# main.net
KiCad netlist of a schematic drawn in EAGLE
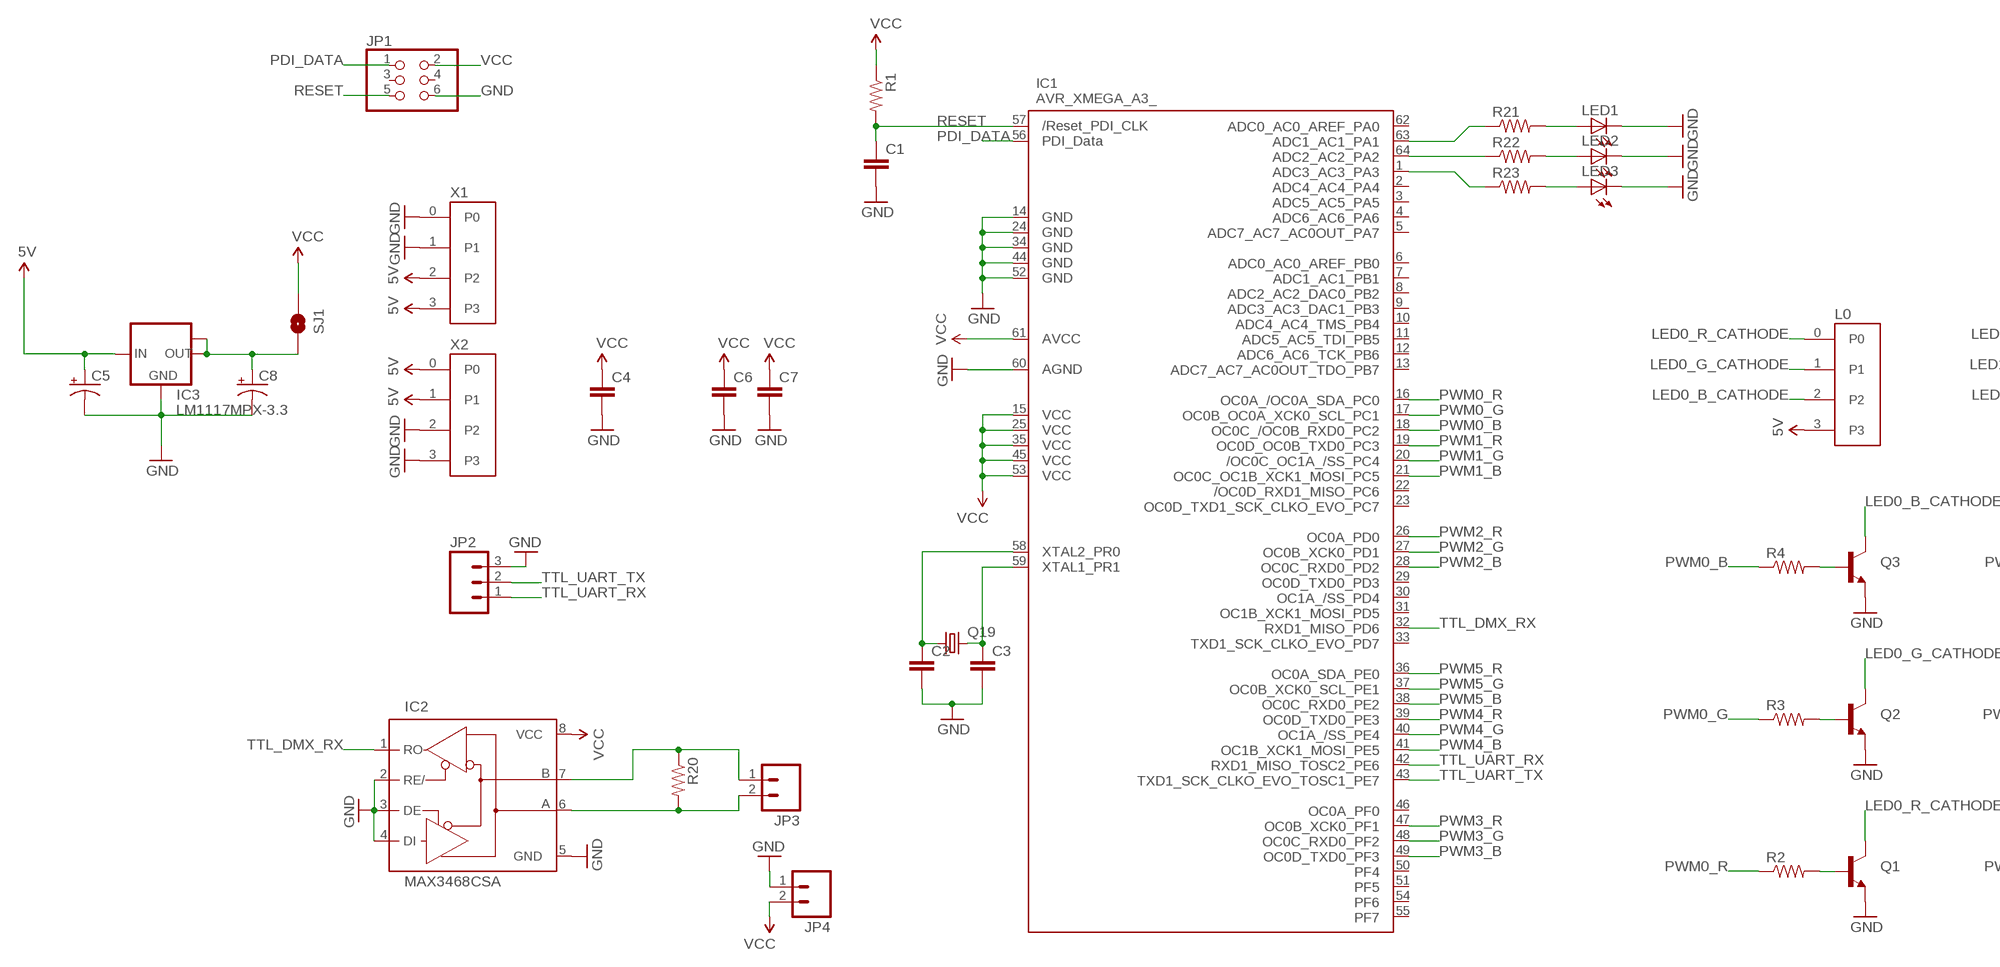
[diagram p0: schematic, sheet 1, part 1 of 2]
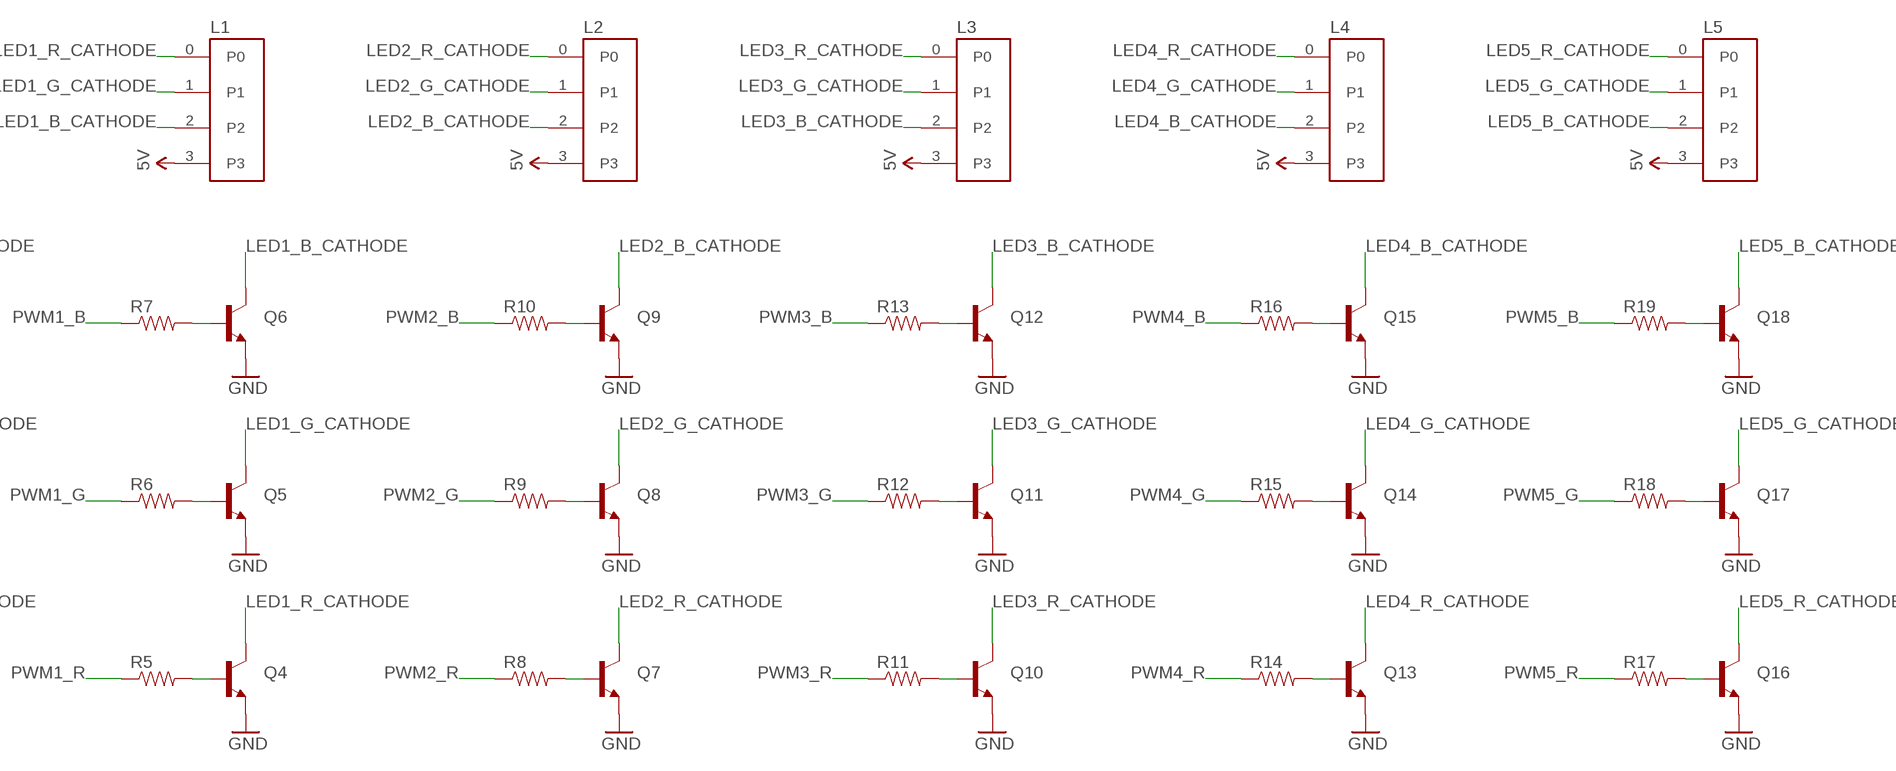
[diagram p1: schematic, sheet 1, part 2 of 2]

(export (version "E")
  (design (tool "Eeschema 10.0.6"))
  (components
    (comp (ref "C1")
      (value "CAP0805")
      (footprint "eagle-import:0805")
      (libsource (lib "eagle-import") (part "CAP0805"))
    )
    (comp (ref "C2")
      (value "CAP0805")
      (footprint "eagle-import:0805")
      (libsource (lib "eagle-import") (part "CAP0805"))
    )
    (comp (ref "C3")
      (value "CAP0805")
      (footprint "eagle-import:0805")
      (libsource (lib "eagle-import") (part "CAP0805"))
    )
    (comp (ref "C4")
      (value "CAP0805")
      (footprint "eagle-import:0805")
      (libsource (lib "eagle-import") (part "CAP0805"))
    )
    (comp (ref "C5")
      (value "CAP_POLSMD")
      (footprint "eagle-import:VISHAY_C")
      (libsource (lib "eagle-import") (part "CAP_POLSMD"))
    )
    (comp (ref "C6")
      (value "CAP0805")
      (footprint "eagle-import:0805")
      (libsource (lib "eagle-import") (part "CAP0805"))
    )
    (comp (ref "C7")
      (value "CAP0805")
      (footprint "eagle-import:0805")
      (libsource (lib "eagle-import") (part "CAP0805"))
    )
    (comp (ref "C8")
      (value "CAP_POLSMD")
      (footprint "eagle-import:VISHAY_C")
      (libsource (lib "eagle-import") (part "CAP_POLSMD"))
    )
    (comp (ref "IC1")
      (value "AVR_XMEGA_A3_")
      (footprint "eagle-import:TQFP64")
      (libsource (lib "eagle-import") (part "AVR_XMEGA_A3_"))
    )
    (comp (ref "IC2")
      (value "MAX3468CSA")
      (footprint "eagle-import:SO08")
      (libsource (lib "eagle-import") (part "MAX34SA68C"))
    )
    (comp (ref "IC3")
      (value "LM1117MPX-3.3")
      (footprint "eagle-import:SOT223")
      (libsource (lib "eagle-import") (part "LM1117MPX-3.3"))
    )
    (comp (ref "JP1")
      (value "PINHD-2X3")
      (footprint "eagle-import:2X03")
      (libsource (lib "eagle-import") (part "PINHD-2X3"))
    )
    (comp (ref "JP2")
      (value "M03LOCK_LONGPADS")
      (footprint "eagle-import:1X03_LOCK_LONGPADS")
      (libsource (lib "eagle-import") (part "M03LOCK_LONGPADS"))
    )
    (comp (ref "JP3")
      (value "M02")
      (footprint "eagle-import:1X02_LONGPADS")
      (libsource (lib "eagle-import") (part "M02"))
    )
    (comp (ref "JP4")
      (value "M02")
      (footprint "eagle-import:1X02_LONGPADS")
      (libsource (lib "eagle-import") (part "M02"))
    )
    (comp (ref "L0")
      (value "SCREW-TERMINAL-4P")
      (footprint "eagle-import:SK-CZZ-4P")
      (libsource (lib "eagle-import") (part "SCREW-TERMINAL-4P"))
    )
    (comp (ref "L1")
      (value "SCREW-TERMINAL-4P")
      (footprint "eagle-import:SK-CZZ-4P")
      (libsource (lib "eagle-import") (part "SCREW-TERMINAL-4P"))
    )
    (comp (ref "L2")
      (value "SCREW-TERMINAL-4P")
      (footprint "eagle-import:SK-CZZ-4P")
      (libsource (lib "eagle-import") (part "SCREW-TERMINAL-4P"))
    )
    (comp (ref "L3")
      (value "SCREW-TERMINAL-4P")
      (footprint "eagle-import:SK-CZZ-4P")
      (libsource (lib "eagle-import") (part "SCREW-TERMINAL-4P"))
    )
    (comp (ref "L4")
      (value "SCREW-TERMINAL-4P")
      (footprint "eagle-import:SK-CZZ-4P")
      (libsource (lib "eagle-import") (part "SCREW-TERMINAL-4P"))
    )
    (comp (ref "L5")
      (value "SCREW-TERMINAL-4P")
      (footprint "eagle-import:SK-CZZ-4P")
      (libsource (lib "eagle-import") (part "SCREW-TERMINAL-4P"))
    )
    (comp (ref "LED1")
      (value "LEDCHIPLED_0805")
      (footprint "eagle-import:CHIPLED_0805")
      (libsource (lib "eagle-import") (part "LEDCHIPLED_0805"))
    )
    (comp (ref "LED2")
      (value "LEDCHIPLED_0805")
      (footprint "eagle-import:CHIPLED_0805")
      (libsource (lib "eagle-import") (part "LEDCHIPLED_0805"))
    )
    (comp (ref "LED3")
      (value "LEDCHIPLED_0805")
      (footprint "eagle-import:CHIPLED_0805")
      (libsource (lib "eagle-import") (part "LEDCHIPLED_0805"))
    )
    (comp (ref "Q1")
      (value "TRANSISTOR_NPNSOT89")
      (footprint "eagle-import:SOT89")
      (libsource (lib "eagle-import") (part "TRANSISTOR_NPNSOT89"))
    )
    (comp (ref "Q2")
      (value "TRANSISTOR_NPNSOT89")
      (footprint "eagle-import:SOT89")
      (libsource (lib "eagle-import") (part "TRANSISTOR_NPNSOT89"))
    )
    (comp (ref "Q3")
      (value "TRANSISTOR_NPNSOT89")
      (footprint "eagle-import:SOT89")
      (libsource (lib "eagle-import") (part "TRANSISTOR_NPNSOT89"))
    )
    (comp (ref "Q4")
      (value "TRANSISTOR_NPNSOT89")
      (footprint "eagle-import:SOT89")
      (libsource (lib "eagle-import") (part "TRANSISTOR_NPNSOT89"))
    )
    (comp (ref "Q5")
      (value "TRANSISTOR_NPNSOT89")
      (footprint "eagle-import:SOT89")
      (libsource (lib "eagle-import") (part "TRANSISTOR_NPNSOT89"))
    )
    (comp (ref "Q6")
      (value "TRANSISTOR_NPNSOT89")
      (footprint "eagle-import:SOT89")
      (libsource (lib "eagle-import") (part "TRANSISTOR_NPNSOT89"))
    )
    (comp (ref "Q7")
      (value "TRANSISTOR_NPNSOT89")
      (footprint "eagle-import:SOT89")
      (libsource (lib "eagle-import") (part "TRANSISTOR_NPNSOT89"))
    )
    (comp (ref "Q8")
      (value "TRANSISTOR_NPNSOT89")
      (footprint "eagle-import:SOT89")
      (libsource (lib "eagle-import") (part "TRANSISTOR_NPNSOT89"))
    )
    (comp (ref "Q9")
      (value "TRANSISTOR_NPNSOT89")
      (footprint "eagle-import:SOT89")
      (libsource (lib "eagle-import") (part "TRANSISTOR_NPNSOT89"))
    )
    (comp (ref "Q10")
      (value "TRANSISTOR_NPNSOT89")
      (footprint "eagle-import:SOT89")
      (libsource (lib "eagle-import") (part "TRANSISTOR_NPNSOT89"))
    )
    (comp (ref "Q11")
      (value "TRANSISTOR_NPNSOT89")
      (footprint "eagle-import:SOT89")
      (libsource (lib "eagle-import") (part "TRANSISTOR_NPNSOT89"))
    )
    (comp (ref "Q12")
      (value "TRANSISTOR_NPNSOT89")
      (footprint "eagle-import:SOT89")
      (libsource (lib "eagle-import") (part "TRANSISTOR_NPNSOT89"))
    )
    (comp (ref "Q13")
      (value "TRANSISTOR_NPNSOT89")
      (footprint "eagle-import:SOT89")
      (libsource (lib "eagle-import") (part "TRANSISTOR_NPNSOT89"))
    )
    (comp (ref "Q14")
      (value "TRANSISTOR_NPNSOT89")
      (footprint "eagle-import:SOT89")
      (libsource (lib "eagle-import") (part "TRANSISTOR_NPNSOT89"))
    )
    (comp (ref "Q15")
      (value "TRANSISTOR_NPNSOT89")
      (footprint "eagle-import:SOT89")
      (libsource (lib "eagle-import") (part "TRANSISTOR_NPNSOT89"))
    )
    (comp (ref "Q16")
      (value "TRANSISTOR_NPNSOT89")
      (footprint "eagle-import:SOT89")
      (libsource (lib "eagle-import") (part "TRANSISTOR_NPNSOT89"))
    )
    (comp (ref "Q17")
      (value "TRANSISTOR_NPNSOT89")
      (footprint "eagle-import:SOT89")
      (libsource (lib "eagle-import") (part "TRANSISTOR_NPNSOT89"))
    )
    (comp (ref "Q18")
      (value "TRANSISTOR_NPNSOT89")
      (footprint "eagle-import:SOT89")
      (libsource (lib "eagle-import") (part "TRANSISTOR_NPNSOT89"))
    )
    (comp (ref "Q19")
      (value "CRYSTALHC49UP")
      (footprint "eagle-import:HC49UP")
      (libsource (lib "eagle-import") (part "CRYSTALHC49UP"))
    )
    (comp (ref "R1")
      (value "RESISTOR")
      (footprint "eagle-import:0805")
      (libsource (lib "eagle-import") (part "RESISTOR"))
    )
    (comp (ref "R2")
      (value "RESISTOR")
      (footprint "eagle-import:0805")
      (libsource (lib "eagle-import") (part "RESISTOR"))
    )
    (comp (ref "R3")
      (value "RESISTOR")
      (footprint "eagle-import:0805")
      (libsource (lib "eagle-import") (part "RESISTOR"))
    )
    (comp (ref "R4")
      (value "RESISTOR")
      (footprint "eagle-import:0805")
      (libsource (lib "eagle-import") (part "RESISTOR"))
    )
    (comp (ref "R5")
      (value "RESISTOR")
      (footprint "eagle-import:0805")
      (libsource (lib "eagle-import") (part "RESISTOR"))
    )
    (comp (ref "R6")
      (value "RESISTOR")
      (footprint "eagle-import:0805")
      (libsource (lib "eagle-import") (part "RESISTOR"))
    )
    (comp (ref "R7")
      (value "RESISTOR")
      (footprint "eagle-import:0805")
      (libsource (lib "eagle-import") (part "RESISTOR"))
    )
    (comp (ref "R8")
      (value "RESISTOR")
      (footprint "eagle-import:0805")
      (libsource (lib "eagle-import") (part "RESISTOR"))
    )
    (comp (ref "R9")
      (value "RESISTOR")
      (footprint "eagle-import:0805")
      (libsource (lib "eagle-import") (part "RESISTOR"))
    )
    (comp (ref "R10")
      (value "RESISTOR")
      (footprint "eagle-import:0805")
      (libsource (lib "eagle-import") (part "RESISTOR"))
    )
    (comp (ref "R11")
      (value "RESISTOR")
      (footprint "eagle-import:0805")
      (libsource (lib "eagle-import") (part "RESISTOR"))
    )
    (comp (ref "R12")
      (value "RESISTOR")
      (footprint "eagle-import:0805")
      (libsource (lib "eagle-import") (part "RESISTOR"))
    )
    (comp (ref "R13")
      (value "RESISTOR")
      (footprint "eagle-import:0805")
      (libsource (lib "eagle-import") (part "RESISTOR"))
    )
    (comp (ref "R14")
      (value "RESISTOR")
      (footprint "eagle-import:0805")
      (libsource (lib "eagle-import") (part "RESISTOR"))
    )
    (comp (ref "R15")
      (value "RESISTOR")
      (footprint "eagle-import:0805")
      (libsource (lib "eagle-import") (part "RESISTOR"))
    )
    (comp (ref "R16")
      (value "RESISTOR")
      (footprint "eagle-import:0805")
      (libsource (lib "eagle-import") (part "RESISTOR"))
    )
    (comp (ref "R17")
      (value "RESISTOR")
      (footprint "eagle-import:0805")
      (libsource (lib "eagle-import") (part "RESISTOR"))
    )
    (comp (ref "R18")
      (value "RESISTOR")
      (footprint "eagle-import:0805")
      (libsource (lib "eagle-import") (part "RESISTOR"))
    )
    (comp (ref "R19")
      (value "RESISTOR")
      (footprint "eagle-import:0805")
      (libsource (lib "eagle-import") (part "RESISTOR"))
    )
    (comp (ref "R20")
      (value "RESISTOR")
      (footprint "eagle-import:0805")
      (libsource (lib "eagle-import") (part "RESISTOR"))
    )
    (comp (ref "R21")
      (value "RESISTOR")
      (footprint "eagle-import:0805")
      (libsource (lib "eagle-import") (part "RESISTOR"))
    )
    (comp (ref "R22")
      (value "RESISTOR")
      (footprint "eagle-import:0805")
      (libsource (lib "eagle-import") (part "RESISTOR"))
    )
    (comp (ref "R23")
      (value "RESISTOR")
      (footprint "eagle-import:0805")
      (libsource (lib "eagle-import") (part "RESISTOR"))
    )
    (comp (ref "SJ1")
      (value "SOLDERJUMPERNO")
      (footprint "eagle-import:SJ_2S-NO")
      (libsource (lib "eagle-import") (part "SOLDERJUMPERNO"))
    )
    (comp (ref "X1")
      (value "SCREW-TERMINAL-4P")
      (footprint "eagle-import:SK-CZZ-4P")
      (libsource (lib "eagle-import") (part "SCREW-TERMINAL-4P"))
    )
    (comp (ref "X2")
      (value "SCREW-TERMINAL-4P")
      (footprint "eagle-import:SK-CZZ-4P")
      (libsource (lib "eagle-import") (part "SCREW-TERMINAL-4P"))
    )
  )
  (nets
    (net (code "1") (name "/LED0_B_CATHODE") (class "Default")
      (node (ref "L0") (pin "2") (pinfunction "P2_2") (pintype "bidirectional"))
      (node (ref "Q3") (pin "2") (pinfunction "C_2") (pintype "passive"))
    )
    (net (code "2") (name "/LED0_G_CATHODE") (class "Default")
      (node (ref "L0") (pin "1") (pinfunction "P1_1") (pintype "bidirectional"))
      (node (ref "Q2") (pin "2") (pinfunction "C_2") (pintype "passive"))
    )
    (net (code "3") (name "/LED0_R_CATHODE") (class "Default")
      (node (ref "L0") (pin "0") (pinfunction "P0_0") (pintype "bidirectional"))
      (node (ref "Q1") (pin "2") (pinfunction "C_2") (pintype "passive"))
    )
    (net (code "4") (name "/LED1_B_CATHODE") (class "Default")
      (node (ref "L1") (pin "2") (pinfunction "P2_2") (pintype "bidirectional"))
      (node (ref "Q6") (pin "2") (pinfunction "C_2") (pintype "passive"))
    )
    (net (code "5") (name "/LED1_G_CATHODE") (class "Default")
      (node (ref "L1") (pin "1") (pinfunction "P1_1") (pintype "bidirectional"))
      (node (ref "Q5") (pin "2") (pinfunction "C_2") (pintype "passive"))
    )
    (net (code "6") (name "/LED1_R_CATHODE") (class "Default")
      (node (ref "L1") (pin "0") (pinfunction "P0_0") (pintype "bidirectional"))
      (node (ref "Q4") (pin "2") (pinfunction "C_2") (pintype "passive"))
    )
    (net (code "7") (name "/LED2_B_CATHODE") (class "Default")
      (node (ref "L2") (pin "2") (pinfunction "P2_2") (pintype "bidirectional"))
      (node (ref "Q9") (pin "2") (pinfunction "C_2") (pintype "passive"))
    )
    (net (code "8") (name "/LED2_G_CATHODE") (class "Default")
      (node (ref "L2") (pin "1") (pinfunction "P1_1") (pintype "bidirectional"))
      (node (ref "Q8") (pin "2") (pinfunction "C_2") (pintype "passive"))
    )
    (net (code "9") (name "/LED2_R_CATHODE") (class "Default")
      (node (ref "L2") (pin "0") (pinfunction "P0_0") (pintype "bidirectional"))
      (node (ref "Q7") (pin "2") (pinfunction "C_2") (pintype "passive"))
    )
    (net (code "10") (name "/LED3_B_CATHODE") (class "Default")
      (node (ref "L3") (pin "2") (pinfunction "P2_2") (pintype "bidirectional"))
      (node (ref "Q12") (pin "2") (pinfunction "C_2") (pintype "passive"))
    )
    (net (code "11") (name "/LED3_G_CATHODE") (class "Default")
      (node (ref "L3") (pin "1") (pinfunction "P1_1") (pintype "bidirectional"))
      (node (ref "Q11") (pin "2") (pinfunction "C_2") (pintype "passive"))
    )
    (net (code "12") (name "/LED3_R_CATHODE") (class "Default")
      (node (ref "L3") (pin "0") (pinfunction "P0_0") (pintype "bidirectional"))
      (node (ref "Q10") (pin "2") (pinfunction "C_2") (pintype "passive"))
    )
    (net (code "13") (name "/LED4_B_CATHODE") (class "Default")
      (node (ref "L4") (pin "2") (pinfunction "P2_2") (pintype "bidirectional"))
      (node (ref "Q15") (pin "2") (pinfunction "C_2") (pintype "passive"))
    )
    (net (code "14") (name "/LED4_G_CATHODE") (class "Default")
      (node (ref "L4") (pin "1") (pinfunction "P1_1") (pintype "bidirectional"))
      (node (ref "Q14") (pin "2") (pinfunction "C_2") (pintype "passive"))
    )
    (net (code "15") (name "/LED4_R_CATHODE") (class "Default")
      (node (ref "L4") (pin "0") (pinfunction "P0_0") (pintype "bidirectional"))
      (node (ref "Q13") (pin "2") (pinfunction "C_2") (pintype "passive"))
    )
    (net (code "16") (name "/LED5_B_CATHODE") (class "Default")
      (node (ref "L5") (pin "2") (pinfunction "P2_2") (pintype "bidirectional"))
      (node (ref "Q18") (pin "2") (pinfunction "C_2") (pintype "passive"))
    )
    (net (code "17") (name "/LED5_G_CATHODE") (class "Default")
      (node (ref "L5") (pin "1") (pinfunction "P1_1") (pintype "bidirectional"))
      (node (ref "Q17") (pin "2") (pinfunction "C_2") (pintype "passive"))
    )
    (net (code "18") (name "/LED5_R_CATHODE") (class "Default")
      (node (ref "L5") (pin "0") (pinfunction "P0_0") (pintype "bidirectional"))
      (node (ref "Q16") (pin "2") (pinfunction "C_2") (pintype "passive"))
    )
    (net (code "19") (name "/PDI_DATA") (class "Default")
      (node (ref "IC1") (pin "56") (pinfunction "PDI_DATA_56") (pintype "bidirectional"))
      (node (ref "JP1") (pin "1") (pinfunction "1_1") (pintype "passive"))
    )
    (net (code "20") (name "/PWM0_B") (class "Default")
      (node (ref "IC1") (pin "18") (pinfunction "PC2_18") (pintype "bidirectional"))
      (node (ref "R4") (pin "1") (pinfunction "1_1") (pintype "passive"))
    )
    (net (code "21") (name "/PWM0_G") (class "Default")
      (node (ref "IC1") (pin "17") (pinfunction "PC1_17") (pintype "bidirectional"))
      (node (ref "R3") (pin "1") (pinfunction "1_1") (pintype "passive"))
    )
    (net (code "22") (name "/PWM0_R") (class "Default")
      (node (ref "IC1") (pin "16") (pinfunction "PC0_16") (pintype "bidirectional"))
      (node (ref "R2") (pin "1") (pinfunction "1_1") (pintype "passive"))
    )
    (net (code "23") (name "/PWM1_B") (class "Default")
      (node (ref "IC1") (pin "21") (pinfunction "PC5_21") (pintype "bidirectional"))
      (node (ref "R7") (pin "1") (pinfunction "1_1") (pintype "passive"))
    )
    (net (code "24") (name "/PWM1_G") (class "Default")
      (node (ref "IC1") (pin "20") (pinfunction "PC4_20") (pintype "bidirectional"))
      (node (ref "R6") (pin "1") (pinfunction "1_1") (pintype "passive"))
    )
    (net (code "25") (name "/PWM1_R") (class "Default")
      (node (ref "IC1") (pin "19") (pinfunction "PC3_19") (pintype "bidirectional"))
      (node (ref "R5") (pin "1") (pinfunction "1_1") (pintype "passive"))
    )
    (net (code "26") (name "/PWM2_B") (class "Default")
      (node (ref "IC1") (pin "28") (pinfunction "PD2_28") (pintype "bidirectional"))
      (node (ref "R10") (pin "1") (pinfunction "1_1") (pintype "passive"))
    )
    (net (code "27") (name "/PWM2_G") (class "Default")
      (node (ref "IC1") (pin "27") (pinfunction "PD1_27") (pintype "bidirectional"))
      (node (ref "R9") (pin "1") (pinfunction "1_1") (pintype "passive"))
    )
    (net (code "28") (name "/PWM2_R") (class "Default")
      (node (ref "IC1") (pin "26") (pinfunction "PD0_26") (pintype "bidirectional"))
      (node (ref "R8") (pin "1") (pinfunction "1_1") (pintype "passive"))
    )
    (net (code "29") (name "/PWM3_B") (class "Default")
      (node (ref "IC1") (pin "49") (pinfunction "PF3_49") (pintype "bidirectional"))
      (node (ref "R13") (pin "1") (pinfunction "1_1") (pintype "passive"))
    )
    (net (code "30") (name "/PWM3_G") (class "Default")
      (node (ref "IC1") (pin "48") (pinfunction "PF2_48") (pintype "bidirectional"))
      (node (ref "R12") (pin "1") (pinfunction "1_1") (pintype "passive"))
    )
    (net (code "31") (name "/PWM3_R") (class "Default")
      (node (ref "IC1") (pin "47") (pinfunction "PF1_47") (pintype "bidirectional"))
      (node (ref "R11") (pin "1") (pinfunction "1_1") (pintype "passive"))
    )
    (net (code "32") (name "/PWM4_B") (class "Default")
      (node (ref "IC1") (pin "41") (pinfunction "PE5_41") (pintype "bidirectional"))
      (node (ref "R16") (pin "1") (pinfunction "1_1") (pintype "passive"))
    )
    (net (code "33") (name "/PWM4_G") (class "Default")
      (node (ref "IC1") (pin "40") (pinfunction "PE4_40") (pintype "bidirectional"))
      (node (ref "R15") (pin "1") (pinfunction "1_1") (pintype "passive"))
    )
    (net (code "34") (name "/PWM4_R") (class "Default")
      (node (ref "IC1") (pin "39") (pinfunction "PE3_39") (pintype "bidirectional"))
      (node (ref "R14") (pin "1") (pinfunction "1_1") (pintype "passive"))
    )
    (net (code "35") (name "/PWM5_B") (class "Default")
      (node (ref "IC1") (pin "38") (pinfunction "PE2_38") (pintype "bidirectional"))
      (node (ref "R19") (pin "1") (pinfunction "1_1") (pintype "passive"))
    )
    (net (code "36") (name "/PWM5_G") (class "Default")
      (node (ref "IC1") (pin "37") (pinfunction "PE1_37") (pintype "bidirectional"))
      (node (ref "R18") (pin "1") (pinfunction "1_1") (pintype "passive"))
    )
    (net (code "37") (name "/PWM5_R") (class "Default")
      (node (ref "IC1") (pin "36") (pinfunction "PE0_36") (pintype "bidirectional"))
      (node (ref "R17") (pin "1") (pinfunction "1_1") (pintype "passive"))
    )
    (net (code "38") (name "/RESET") (class "Default")
      (node (ref "C1") (pin "1") (pinfunction "1_1") (pintype "passive"))
      (node (ref "IC1") (pin "57") (pinfunction "RESET_57") (pintype "bidirectional"))
      (node (ref "JP1") (pin "5") (pinfunction "5_5") (pintype "passive"))
      (node (ref "R1") (pin "2") (pinfunction "2_2") (pintype "passive"))
    )
    (net (code "39") (name "/TTL_DMX_RX") (class "Default")
      (node (ref "IC1") (pin "32") (pinfunction "PD6_32") (pintype "bidirectional"))
      (node (ref "IC2") (pin "1") (pinfunction "RO_1") (pintype "output"))
    )
    (net (code "40") (name "/TTL_UART_RX") (class "Default")
      (node (ref "IC1") (pin "42") (pinfunction "PE6_42") (pintype "bidirectional"))
      (node (ref "JP2") (pin "1") (pinfunction "1_1") (pintype "passive"))
    )
    (net (code "41") (name "/TTL_UART_TX") (class "Default")
      (node (ref "IC1") (pin "43") (pinfunction "PE7_43") (pintype "bidirectional"))
      (node (ref "JP2") (pin "2") (pinfunction "2_2") (pintype "passive"))
    )
    (net (code "42") (name "5V") (class "Default")
      (node (ref "C5") (pin "+") (pinfunction "+_+") (pintype "passive"))
      (node (ref "IC3") (pin "3") (pinfunction "IN_3") (pintype "input"))
      (node (ref "L0") (pin "3") (pinfunction "P3_3") (pintype "bidirectional"))
      (node (ref "L1") (pin "3") (pinfunction "P3_3") (pintype "bidirectional"))
      (node (ref "L2") (pin "3") (pinfunction "P3_3") (pintype "bidirectional"))
      (node (ref "L3") (pin "3") (pinfunction "P3_3") (pintype "bidirectional"))
      (node (ref "L4") (pin "3") (pinfunction "P3_3") (pintype "bidirectional"))
      (node (ref "L5") (pin "3") (pinfunction "P3_3") (pintype "bidirectional"))
      (node (ref "X1") (pin "2") (pinfunction "P2_2") (pintype "bidirectional"))
      (node (ref "X1") (pin "3") (pinfunction "P3_3") (pintype "bidirectional"))
      (node (ref "X2") (pin "0") (pinfunction "P0_0") (pintype "bidirectional"))
      (node (ref "X2") (pin "1") (pinfunction "P1_1") (pintype "bidirectional"))
    )
    (net (code "43") (name "GND") (class "Default")
      (node (ref "C1") (pin "2") (pinfunction "2_2") (pintype "passive"))
      (node (ref "C2") (pin "2") (pinfunction "2_2") (pintype "passive"))
      (node (ref "C3") (pin "2") (pinfunction "2_2") (pintype "passive"))
      (node (ref "C4") (pin "2") (pinfunction "2_2") (pintype "passive"))
      (node (ref "C5") (pin "-") (pinfunction "-_-") (pintype "passive"))
      (node (ref "C6") (pin "2") (pinfunction "2_2") (pintype "passive"))
      (node (ref "C7") (pin "2") (pinfunction "2_2") (pintype "passive"))
      (node (ref "C8") (pin "-") (pinfunction "-_-") (pintype "passive"))
      (node (ref "IC1") (pin "14") (pinfunction "GND1_14") (pintype "bidirectional"))
      (node (ref "IC1") (pin "24") (pinfunction "GND2_24") (pintype "bidirectional"))
      (node (ref "IC1") (pin "34") (pinfunction "GND3_34") (pintype "bidirectional"))
      (node (ref "IC1") (pin "44") (pinfunction "GND4_44") (pintype "bidirectional"))
      (node (ref "IC1") (pin "52") (pinfunction "GND5_52") (pintype "bidirectional"))
      (node (ref "IC1") (pin "60") (pinfunction "AGND_60") (pintype "bidirectional"))
      (node (ref "IC2") (pin "2") (pinfunction "RE/_2") (pintype "input"))
      (node (ref "IC2") (pin "3") (pinfunction "DE_3") (pintype "input"))
      (node (ref "IC2") (pin "4") (pinfunction "DI_4") (pintype "input"))
      (node (ref "IC2") (pin "5") (pinfunction "GND_5") (pintype "power_in"))
      (node (ref "IC3") (pin "1") (pinfunction "GND_1") (pintype "input"))
      (node (ref "JP1") (pin "6") (pinfunction "6_6") (pintype "passive"))
      (node (ref "JP2") (pin "3") (pinfunction "3_3") (pintype "passive"))
      (node (ref "JP4") (pin "1") (pinfunction "1_1") (pintype "passive"))
      (node (ref "LED1") (pin "C") (pinfunction "C_C") (pintype "passive"))
      (node (ref "LED2") (pin "C") (pinfunction "C_C") (pintype "passive"))
      (node (ref "LED3") (pin "C") (pinfunction "C_C") (pintype "passive"))
      (node (ref "Q1") (pin "3") (pinfunction "E_3") (pintype "passive"))
      (node (ref "Q10") (pin "3") (pinfunction "E_3") (pintype "passive"))
      (node (ref "Q11") (pin "3") (pinfunction "E_3") (pintype "passive"))
      (node (ref "Q12") (pin "3") (pinfunction "E_3") (pintype "passive"))
      (node (ref "Q13") (pin "3") (pinfunction "E_3") (pintype "passive"))
      (node (ref "Q14") (pin "3") (pinfunction "E_3") (pintype "passive"))
      (node (ref "Q15") (pin "3") (pinfunction "E_3") (pintype "passive"))
      (node (ref "Q16") (pin "3") (pinfunction "E_3") (pintype "passive"))
      (node (ref "Q17") (pin "3") (pinfunction "E_3") (pintype "passive"))
      (node (ref "Q18") (pin "3") (pinfunction "E_3") (pintype "passive"))
      (node (ref "Q2") (pin "3") (pinfunction "E_3") (pintype "passive"))
      (node (ref "Q3") (pin "3") (pinfunction "E_3") (pintype "passive"))
      (node (ref "Q4") (pin "3") (pinfunction "E_3") (pintype "passive"))
      (node (ref "Q5") (pin "3") (pinfunction "E_3") (pintype "passive"))
      (node (ref "Q6") (pin "3") (pinfunction "E_3") (pintype "passive"))
      (node (ref "Q7") (pin "3") (pinfunction "E_3") (pintype "passive"))
      (node (ref "Q8") (pin "3") (pinfunction "E_3") (pintype "passive"))
      (node (ref "Q9") (pin "3") (pinfunction "E_3") (pintype "passive"))
      (node (ref "X1") (pin "0") (pinfunction "P0_0") (pintype "bidirectional"))
      (node (ref "X1") (pin "1") (pinfunction "P1_1") (pintype "bidirectional"))
      (node (ref "X2") (pin "2") (pinfunction "P2_2") (pintype "bidirectional"))
      (node (ref "X2") (pin "3") (pinfunction "P3_3") (pintype "bidirectional"))
    )
    (net (code "44") (name "Net-(IC1-PA1)") (class "Default")
      (node (ref "IC1") (pin "63") (pinfunction "PA1_63") (pintype "bidirectional"))
      (node (ref "R21") (pin "1") (pinfunction "1_1") (pintype "passive"))
    )
    (net (code "45") (name "Net-(IC1-PA2)") (class "Default")
      (node (ref "IC1") (pin "64") (pinfunction "PA2_64") (pintype "bidirectional"))
      (node (ref "R22") (pin "1") (pinfunction "1_1") (pintype "passive"))
    )
    (net (code "46") (name "Net-(IC1-PA3)") (class "Default")
      (node (ref "IC1") (pin "1") (pinfunction "PA3_1") (pintype "bidirectional"))
      (node (ref "R23") (pin "1") (pinfunction "1_1") (pintype "passive"))
    )
    (net (code "47") (name "Net-(IC1-PR0)") (class "Default")
      (node (ref "C2") (pin "1") (pinfunction "1_1") (pintype "passive"))
      (node (ref "IC1") (pin "58") (pinfunction "PR0_58") (pintype "bidirectional"))
      (node (ref "Q19") (pin "1") (pinfunction "1_1") (pintype "passive"))
    )
    (net (code "48") (name "Net-(IC1-PR1)") (class "Default")
      (node (ref "C3") (pin "1") (pinfunction "1_1") (pintype "passive"))
      (node (ref "IC1") (pin "59") (pinfunction "PR1_59") (pintype "bidirectional"))
      (node (ref "Q19") (pin "2") (pinfunction "2_2") (pintype "passive"))
    )
    (net (code "49") (name "Net-(IC2-A)") (class "Default")
      (node (ref "IC2") (pin "6") (pinfunction "A_6") (pintype "passive"))
      (node (ref "JP3") (pin "2") (pinfunction "2_2") (pintype "passive"))
      (node (ref "R20") (pin "2") (pinfunction "2_2") (pintype "passive"))
    )
    (net (code "50") (name "Net-(IC2-B)") (class "Default")
      (node (ref "IC2") (pin "7") (pinfunction "B_7") (pintype "passive"))
      (node (ref "JP3") (pin "1") (pinfunction "1_1") (pintype "passive"))
      (node (ref "R20") (pin "1") (pinfunction "1_1") (pintype "passive"))
    )
    (net (code "51") (name "Net-(IC3-OUT)") (class "Default")
      (node (ref "C8") (pin "+") (pinfunction "+_+") (pintype "passive"))
      (node (ref "IC3") (pin "2") (pinfunction "OUT_2") (pintype "passive"))
      (node (ref "IC3") (pin "TAB") (pinfunction "OUT1_TAB") (pintype "passive"))
      (node (ref "SJ1") (pin "2") (pinfunction "2_2") (pintype "passive"))
    )
    (net (code "52") (name "Net-(LED1-PadA)") (class "Default")
      (node (ref "LED1") (pin "A") (pinfunction "A_A") (pintype "passive"))
      (node (ref "R21") (pin "2") (pinfunction "2_2") (pintype "passive"))
    )
    (net (code "53") (name "Net-(LED2-PadA)") (class "Default")
      (node (ref "LED2") (pin "A") (pinfunction "A_A") (pintype "passive"))
      (node (ref "R22") (pin "2") (pinfunction "2_2") (pintype "passive"))
    )
    (net (code "54") (name "Net-(LED3-PadA)") (class "Default")
      (node (ref "LED3") (pin "A") (pinfunction "A_A") (pintype "passive"))
      (node (ref "R23") (pin "2") (pinfunction "2_2") (pintype "passive"))
    )
    (net (code "55") (name "Net-(Q1-B)") (class "Default")
      (node (ref "Q1") (pin "1") (pinfunction "B_1") (pintype "passive"))
      (node (ref "R2") (pin "2") (pinfunction "2_2") (pintype "passive"))
    )
    (net (code "56") (name "Net-(Q2-B)") (class "Default")
      (node (ref "Q2") (pin "1") (pinfunction "B_1") (pintype "passive"))
      (node (ref "R3") (pin "2") (pinfunction "2_2") (pintype "passive"))
    )
    (net (code "57") (name "Net-(Q3-B)") (class "Default")
      (node (ref "Q3") (pin "1") (pinfunction "B_1") (pintype "passive"))
      (node (ref "R4") (pin "2") (pinfunction "2_2") (pintype "passive"))
    )
    (net (code "58") (name "Net-(Q4-B)") (class "Default")
      (node (ref "Q4") (pin "1") (pinfunction "B_1") (pintype "passive"))
      (node (ref "R5") (pin "2") (pinfunction "2_2") (pintype "passive"))
    )
    (net (code "59") (name "Net-(Q5-B)") (class "Default")
      (node (ref "Q5") (pin "1") (pinfunction "B_1") (pintype "passive"))
      (node (ref "R6") (pin "2") (pinfunction "2_2") (pintype "passive"))
    )
    (net (code "60") (name "Net-(Q6-B)") (class "Default")
      (node (ref "Q6") (pin "1") (pinfunction "B_1") (pintype "passive"))
      (node (ref "R7") (pin "2") (pinfunction "2_2") (pintype "passive"))
    )
    (net (code "61") (name "Net-(Q7-B)") (class "Default")
      (node (ref "Q7") (pin "1") (pinfunction "B_1") (pintype "passive"))
      (node (ref "R8") (pin "2") (pinfunction "2_2") (pintype "passive"))
    )
    (net (code "62") (name "Net-(Q8-B)") (class "Default")
      (node (ref "Q8") (pin "1") (pinfunction "B_1") (pintype "passive"))
      (node (ref "R9") (pin "2") (pinfunction "2_2") (pintype "passive"))
    )
    (net (code "63") (name "Net-(Q9-B)") (class "Default")
      (node (ref "Q9") (pin "1") (pinfunction "B_1") (pintype "passive"))
      (node (ref "R10") (pin "2") (pinfunction "2_2") (pintype "passive"))
    )
    (net (code "64") (name "Net-(Q10-B)") (class "Default")
      (node (ref "Q10") (pin "1") (pinfunction "B_1") (pintype "passive"))
      (node (ref "R11") (pin "2") (pinfunction "2_2") (pintype "passive"))
    )
    (net (code "65") (name "Net-(Q11-B)") (class "Default")
      (node (ref "Q11") (pin "1") (pinfunction "B_1") (pintype "passive"))
      (node (ref "R12") (pin "2") (pinfunction "2_2") (pintype "passive"))
    )
    (net (code "66") (name "Net-(Q12-B)") (class "Default")
      (node (ref "Q12") (pin "1") (pinfunction "B_1") (pintype "passive"))
      (node (ref "R13") (pin "2") (pinfunction "2_2") (pintype "passive"))
    )
    (net (code "67") (name "Net-(Q13-B)") (class "Default")
      (node (ref "Q13") (pin "1") (pinfunction "B_1") (pintype "passive"))
      (node (ref "R14") (pin "2") (pinfunction "2_2") (pintype "passive"))
    )
    (net (code "68") (name "Net-(Q14-B)") (class "Default")
      (node (ref "Q14") (pin "1") (pinfunction "B_1") (pintype "passive"))
      (node (ref "R15") (pin "2") (pinfunction "2_2") (pintype "passive"))
    )
    (net (code "69") (name "Net-(Q15-B)") (class "Default")
      (node (ref "Q15") (pin "1") (pinfunction "B_1") (pintype "passive"))
      (node (ref "R16") (pin "2") (pinfunction "2_2") (pintype "passive"))
    )
    (net (code "70") (name "Net-(Q16-B)") (class "Default")
      (node (ref "Q16") (pin "1") (pinfunction "B_1") (pintype "passive"))
      (node (ref "R17") (pin "2") (pinfunction "2_2") (pintype "passive"))
    )
    (net (code "71") (name "Net-(Q17-B)") (class "Default")
      (node (ref "Q17") (pin "1") (pinfunction "B_1") (pintype "passive"))
      (node (ref "R18") (pin "2") (pinfunction "2_2") (pintype "passive"))
    )
    (net (code "72") (name "Net-(Q18-B)") (class "Default")
      (node (ref "Q18") (pin "1") (pinfunction "B_1") (pintype "passive"))
      (node (ref "R19") (pin "2") (pinfunction "2_2") (pintype "passive"))
    )
    (net (code "73") (name "VCC") (class "Default")
      (node (ref "C4") (pin "1") (pinfunction "1_1") (pintype "passive"))
      (node (ref "C6") (pin "1") (pinfunction "1_1") (pintype "passive"))
      (node (ref "C7") (pin "1") (pinfunction "1_1") (pintype "passive"))
      (node (ref "IC1") (pin "15") (pinfunction "VCC1_15") (pintype "bidirectional"))
      (node (ref "IC1") (pin "25") (pinfunction "VCC2_25") (pintype "bidirectional"))
      (node (ref "IC1") (pin "35") (pinfunction "VCC3_35") (pintype "bidirectional"))
      (node (ref "IC1") (pin "45") (pinfunction "VCC4_45") (pintype "bidirectional"))
      (node (ref "IC1") (pin "53") (pinfunction "VCC5_53") (pintype "bidirectional"))
      (node (ref "IC1") (pin "61") (pinfunction "AVCC_61") (pintype "bidirectional"))
      (node (ref "IC2") (pin "8") (pinfunction "VCC_8") (pintype "power_in"))
      (node (ref "JP1") (pin "2") (pinfunction "2_2") (pintype "passive"))
      (node (ref "JP4") (pin "2") (pinfunction "2_2") (pintype "passive"))
      (node (ref "R1") (pin "1") (pinfunction "1_1") (pintype "passive"))
      (node (ref "SJ1") (pin "1") (pinfunction "1_1") (pintype "passive"))
    )
    (net (code "74") (name "unconnected-(IC1-PA0-Pad62)") (class "Default")
      (node (ref "IC1") (pin "62") (pinfunction "PA0_62") (pintype "bidirectional"))
    )
    (net (code "75") (name "unconnected-(IC1-PA4-Pad2)") (class "Default")
      (node (ref "IC1") (pin "2") (pinfunction "PA4_2") (pintype "bidirectional"))
    )
    (net (code "76") (name "unconnected-(IC1-PA5-Pad3)") (class "Default")
      (node (ref "IC1") (pin "3") (pinfunction "PA5_3") (pintype "bidirectional"))
    )
    (net (code "77") (name "unconnected-(IC1-PA6-Pad4)") (class "Default")
      (node (ref "IC1") (pin "4") (pinfunction "PA6_4") (pintype "bidirectional"))
    )
    (net (code "78") (name "unconnected-(IC1-PA7-Pad5)") (class "Default")
      (node (ref "IC1") (pin "5") (pinfunction "PA7_5") (pintype "bidirectional"))
    )
    (net (code "79") (name "unconnected-(IC1-PB0-Pad6)") (class "Default")
      (node (ref "IC1") (pin "6") (pinfunction "PB0_6") (pintype "bidirectional"))
    )
    (net (code "80") (name "unconnected-(IC1-PB1-Pad7)") (class "Default")
      (node (ref "IC1") (pin "7") (pinfunction "PB1_7") (pintype "bidirectional"))
    )
    (net (code "81") (name "unconnected-(IC1-PB2-Pad8)") (class "Default")
      (node (ref "IC1") (pin "8") (pinfunction "PB2_8") (pintype "bidirectional"))
    )
    (net (code "82") (name "unconnected-(IC1-PB3-Pad9)") (class "Default")
      (node (ref "IC1") (pin "9") (pinfunction "PB3_9") (pintype "bidirectional"))
    )
    (net (code "83") (name "unconnected-(IC1-PB4-Pad10)") (class "Default")
      (node (ref "IC1") (pin "10") (pinfunction "PB4_10") (pintype "bidirectional"))
    )
    (net (code "84") (name "unconnected-(IC1-PB5-Pad11)") (class "Default")
      (node (ref "IC1") (pin "11") (pinfunction "PB5_11") (pintype "bidirectional"))
    )
    (net (code "85") (name "unconnected-(IC1-PB6-Pad12)") (class "Default")
      (node (ref "IC1") (pin "12") (pinfunction "PB6_12") (pintype "bidirectional"))
    )
    (net (code "86") (name "unconnected-(IC1-PB7-Pad13)") (class "Default")
      (node (ref "IC1") (pin "13") (pinfunction "PB7_13") (pintype "bidirectional"))
    )
    (net (code "87") (name "unconnected-(IC1-PC6-Pad22)") (class "Default")
      (node (ref "IC1") (pin "22") (pinfunction "PC6_22") (pintype "bidirectional"))
    )
    (net (code "88") (name "unconnected-(IC1-PC7-Pad23)") (class "Default")
      (node (ref "IC1") (pin "23") (pinfunction "PC7_23") (pintype "bidirectional"))
    )
    (net (code "89") (name "unconnected-(IC1-PD3-Pad29)") (class "Default")
      (node (ref "IC1") (pin "29") (pinfunction "PD3_29") (pintype "bidirectional"))
    )
    (net (code "90") (name "unconnected-(IC1-PD4-Pad30)") (class "Default")
      (node (ref "IC1") (pin "30") (pinfunction "PD4_30") (pintype "bidirectional"))
    )
    (net (code "91") (name "unconnected-(IC1-PD5-Pad31)") (class "Default")
      (node (ref "IC1") (pin "31") (pinfunction "PD5_31") (pintype "bidirectional"))
    )
    (net (code "92") (name "unconnected-(IC1-PD7-Pad33)") (class "Default")
      (node (ref "IC1") (pin "33") (pinfunction "PD7_33") (pintype "bidirectional"))
    )
    (net (code "93") (name "unconnected-(IC1-PF0-Pad46)") (class "Default")
      (node (ref "IC1") (pin "46") (pinfunction "PF0_46") (pintype "bidirectional"))
    )
    (net (code "94") (name "unconnected-(IC1-PF4-Pad50)") (class "Default")
      (node (ref "IC1") (pin "50") (pinfunction "PF4_50") (pintype "bidirectional"))
    )
    (net (code "95") (name "unconnected-(IC1-PF5-Pad51)") (class "Default")
      (node (ref "IC1") (pin "51") (pinfunction "PF5_51") (pintype "bidirectional"))
    )
    (net (code "96") (name "unconnected-(IC1-PF6-Pad54)") (class "Default")
      (node (ref "IC1") (pin "54") (pinfunction "PF6_54") (pintype "bidirectional"))
    )
    (net (code "97") (name "unconnected-(IC1-PF7-Pad55)") (class "Default")
      (node (ref "IC1") (pin "55") (pinfunction "PF7_55") (pintype "bidirectional"))
    )
    (net (code "98") (name "unconnected-(JP1-Pad3)") (class "Default")
      (node (ref "JP1") (pin "3") (pinfunction "3_3") (pintype "passive"))
    )
    (net (code "99") (name "unconnected-(JP1-Pad4)") (class "Default")
      (node (ref "JP1") (pin "4") (pinfunction "4_4") (pintype "passive"))
    )
  )
)
